# MOSFET_JUNCTION.net
KiCad netlist of a schematic drawn in Altium Designer
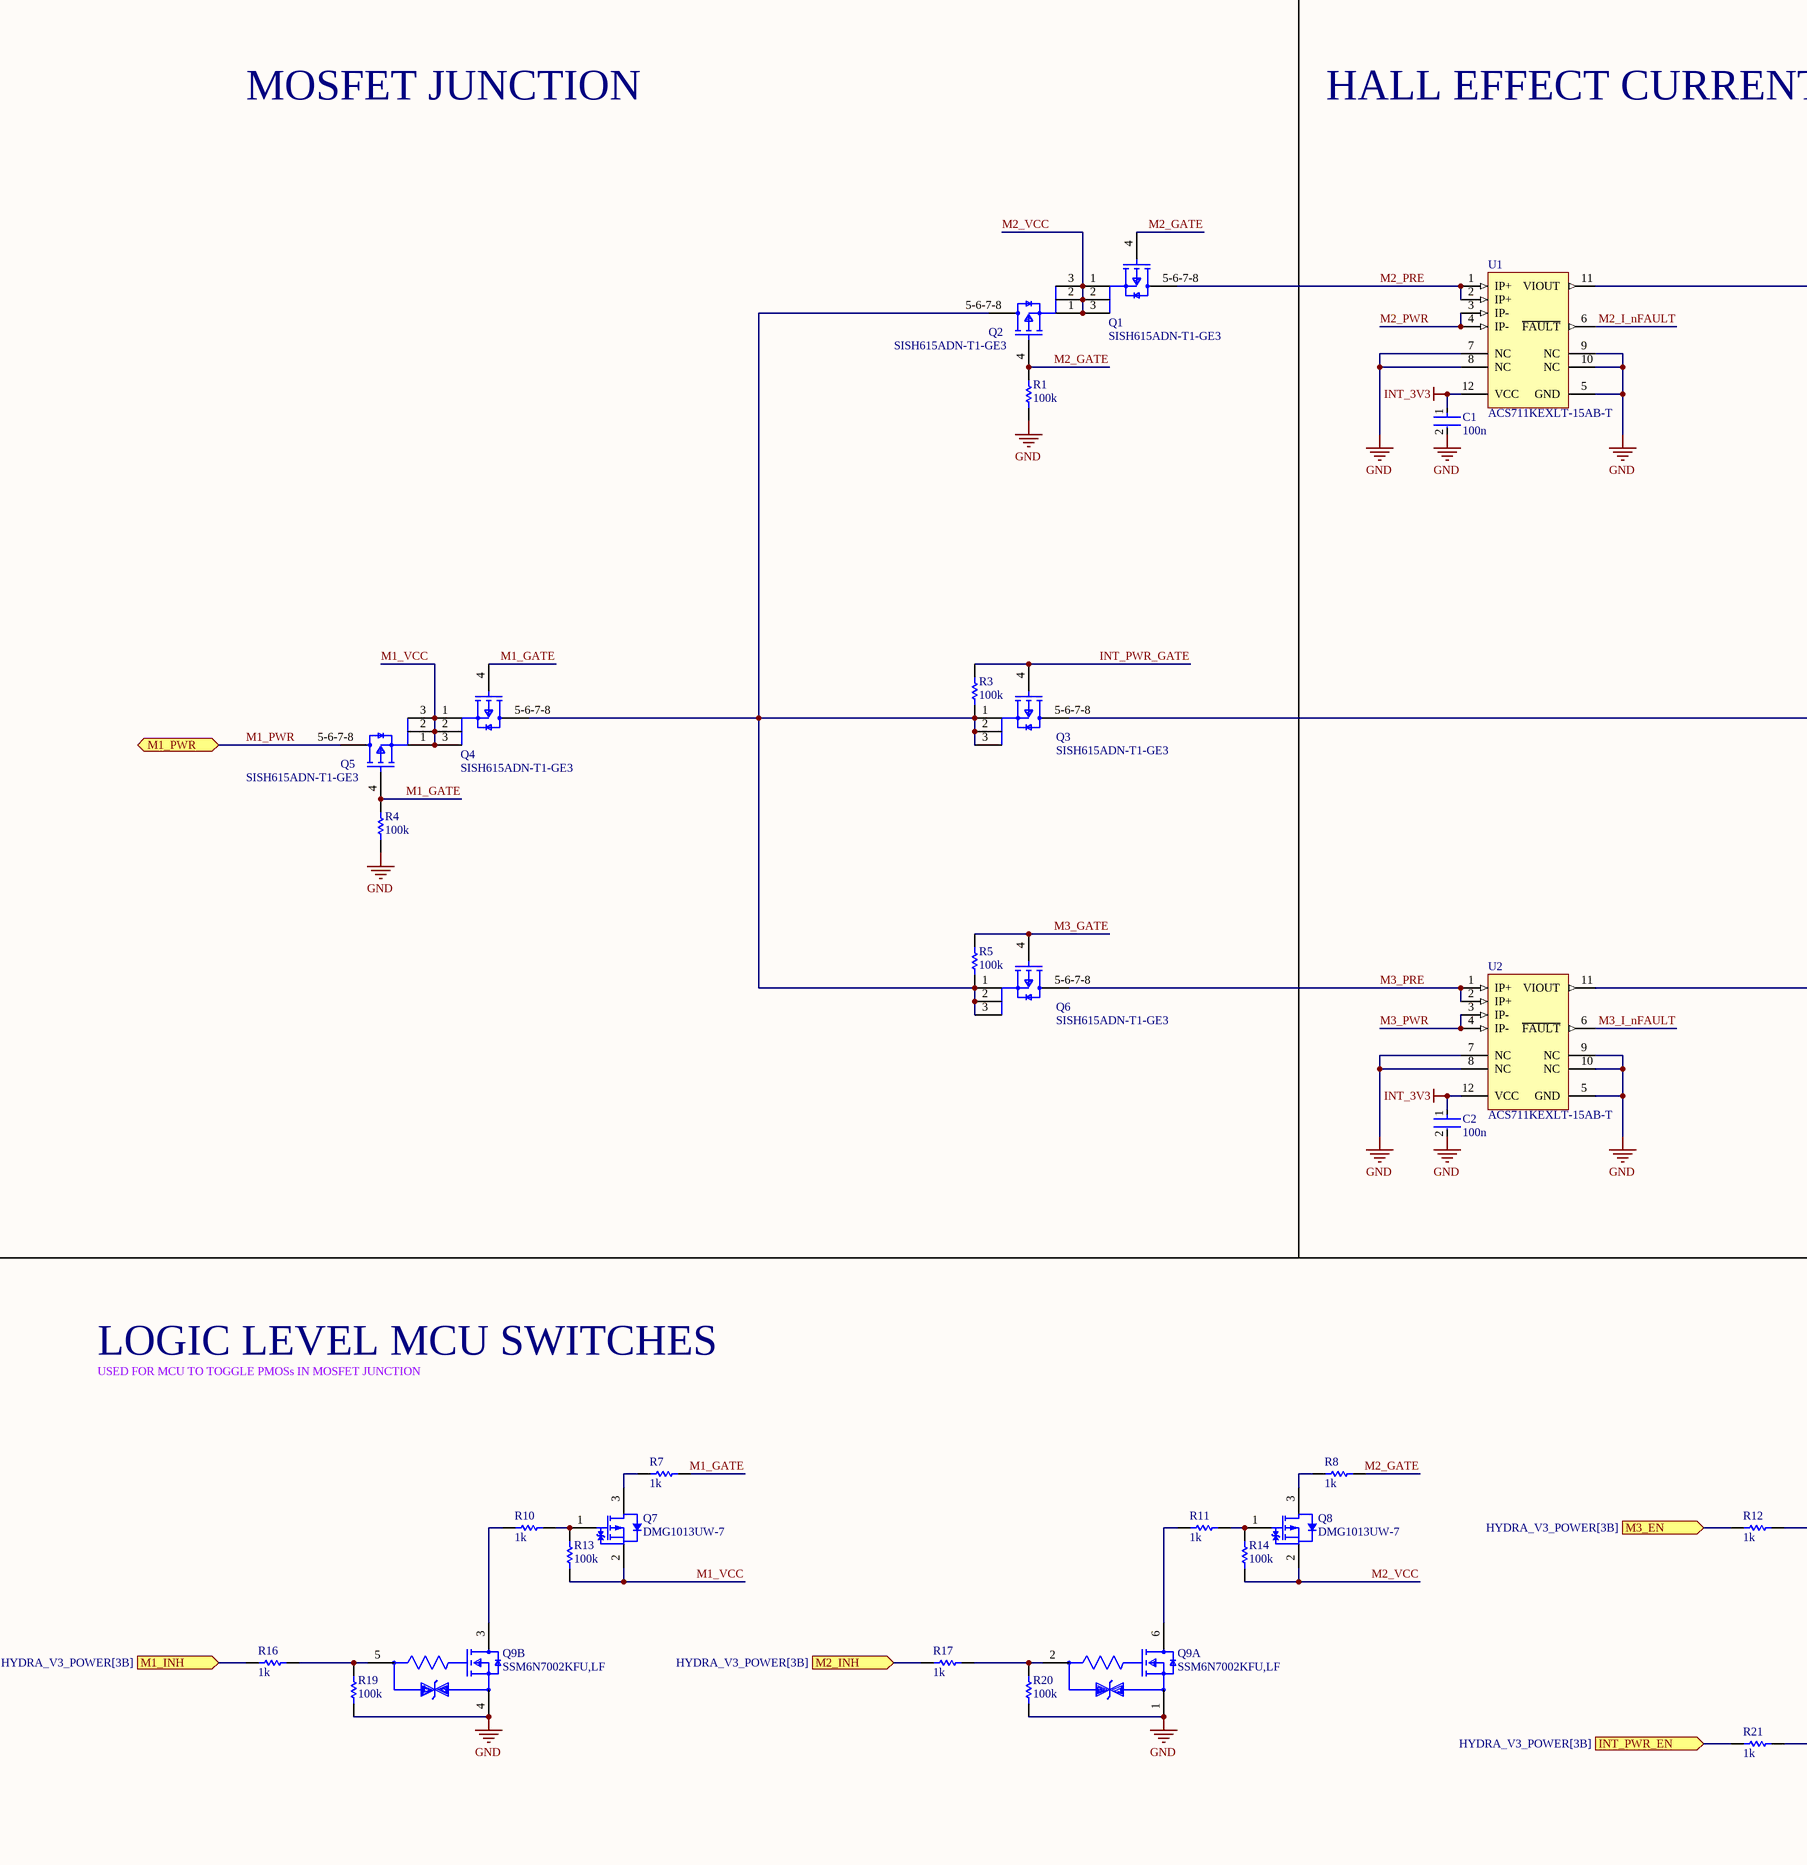
[diagram p0: MOSFET_JUNCTION.SchDoc, left]
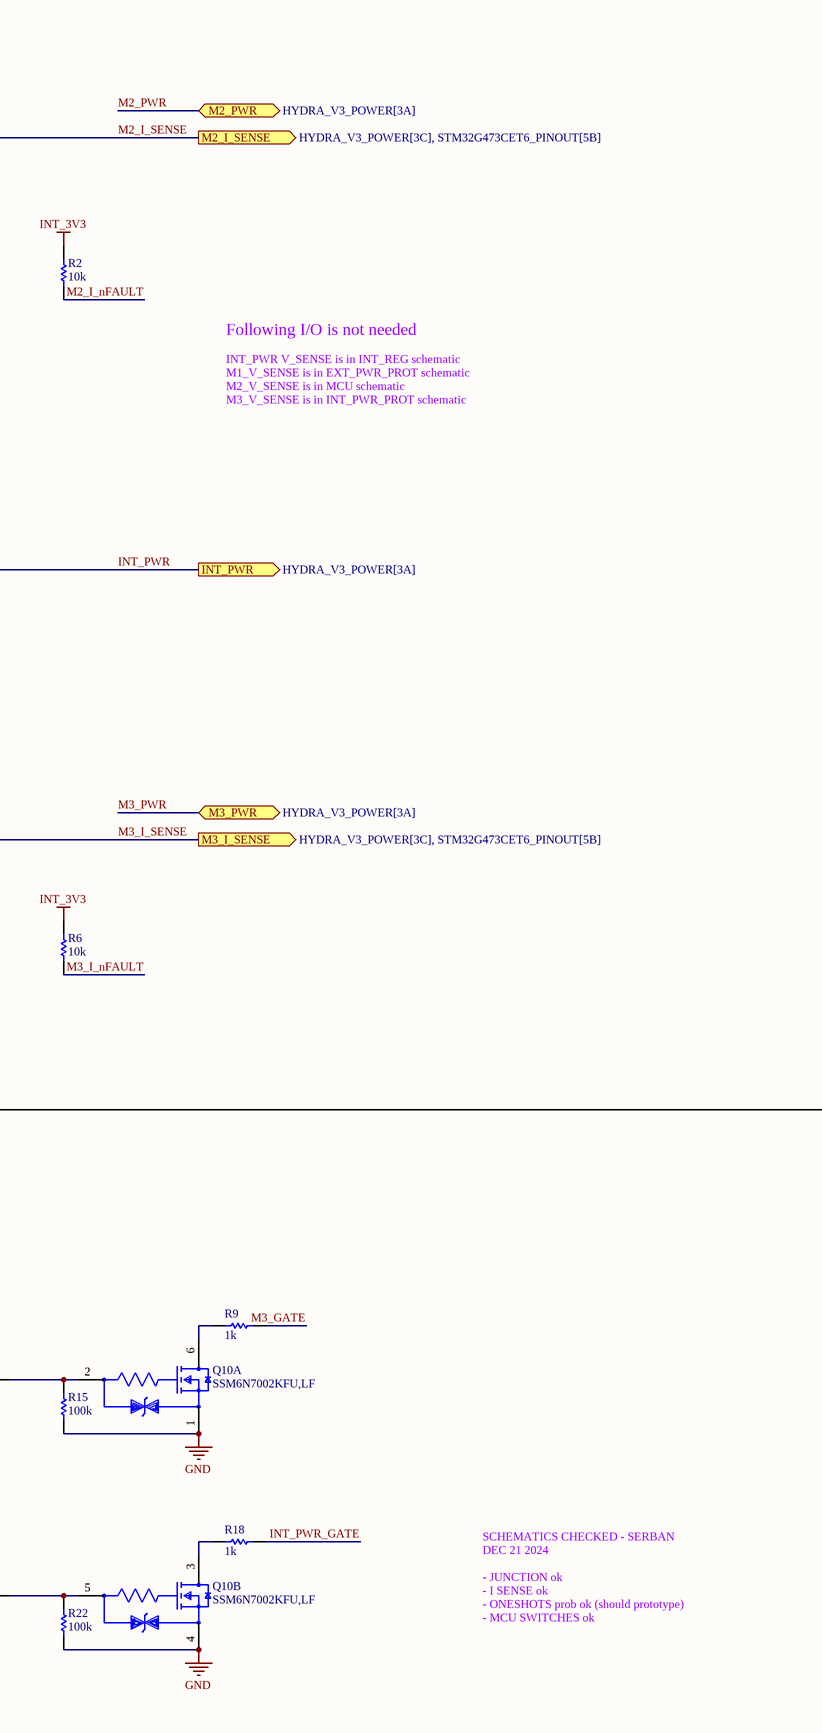
[diagram p1: MOSFET_JUNCTION.SchDoc, right]

(export (version "E")
  (design (tool "Eeschema 10.0.6"))
  (components
    (comp (ref "C1")
      (value "100n")
      (footprint "FP-0402-L_1_0_0_05-W_0_5-IPC_A")
      (description "LARGE PADS, 0402 CAP, CHANGE COMMENT TO MATCH REAL P/N")
      (libsource (lib "Space Concordia") (part "b4654b650e69147ec39a6b967a45e02"))
    )
    (comp (ref "C2")
      (value "100n")
      (footprint "FP-0402-L_1_0_0_05-W_0_5-IPC_A")
      (description "LARGE PADS, 0402 CAP, CHANGE COMMENT TO MATCH REAL P/N")
      (libsource (lib "Space Concordia") (part "b4654b650e69147ec39a6b967a45e02"))
    )
    (comp (ref "Q1")
      (value "SISH615ADN-T1-GE3")
      (footprint "SISH615ADN-T1-GE3-Footprint-1")
      (description "Trans MOSFET P-CH 20V 22.1A 8-Pin PowerPAK 1212 EP T/R")
      (libsource (lib "Space Concordia") (part "CMP-013-00036-4"))
    )
    (comp (ref "Q2")
      (value "SISH615ADN-T1-GE3")
      (footprint "SISH615ADN-T1-GE3-Footprint-1")
      (description "Trans MOSFET P-CH 20V 22.1A 8-Pin PowerPAK 1212 EP T/R")
      (libsource (lib "Space Concordia") (part "CMP-013-00036-4"))
    )
    (comp (ref "Q3")
      (value "SISH615ADN-T1-GE3")
      (footprint "SISH615ADN-T1-GE3-Footprint-1")
      (description "Trans MOSFET P-CH 20V 22.1A 8-Pin PowerPAK 1212 EP T/R")
      (libsource (lib "Space Concordia") (part "CMP-013-00036-4"))
    )
    (comp (ref "Q4")
      (value "SISH615ADN-T1-GE3")
      (footprint "SISH615ADN-T1-GE3-Footprint-1")
      (description "Trans MOSFET P-CH 20V 22.1A 8-Pin PowerPAK 1212 EP T/R")
      (libsource (lib "Space Concordia") (part "CMP-013-00036-4"))
    )
    (comp (ref "Q5")
      (value "SISH615ADN-T1-GE3")
      (footprint "SISH615ADN-T1-GE3-Footprint-1")
      (description "Trans MOSFET P-CH 20V 22.1A 8-Pin PowerPAK 1212 EP T/R")
      (libsource (lib "Space Concordia") (part "CMP-013-00036-4"))
    )
    (comp (ref "Q6")
      (value "SISH615ADN-T1-GE3")
      (footprint "SISH615ADN-T1-GE3-Footprint-1")
      (description "Trans MOSFET P-CH 20V 22.1A 8-Pin PowerPAK 1212 EP T/R")
      (libsource (lib "Space Concordia") (part "CMP-013-00036-4"))
    )
    (comp (ref "Q7")
      (value "DMG1013UW-7")
      (footprint "DIOD-SOT323-3_V")
      (fields (field (name "MANUFACTURER") "Diodes Inc"))
      (libsource (lib "Altium Content Vault") (part "PEMOS-GSD-3_C"))
    )
    (comp (ref "Q8")
      (value "DMG1013UW-7")
      (footprint "DIOD-SOT323-3_V")
      (fields (field (name "MANUFACTURER") "Diodes Inc"))
      (libsource (lib "Altium Content Vault") (part "PEMOS-GSD-3_C"))
    )
    (comp (ref "Q9")
      (value "SSM6N7002KFU,LF")
      (footprint "FP-SSOP6-P-0_65A-MFG")
      (description "MOSFET 2N-CH 60V 0.3A")
      (libsource (lib "Altium Content Vault") (part "088aa6ac103fdeebe0d1c52ece6b7b9"))
    )
    (comp (ref "Q10")
      (value "SSM6N7002KFU,LF")
      (footprint "FP-SSOP6-P-0_65A-MFG")
      (description "MOSFET 2N-CH 60V 0.3A")
      (libsource (lib "Altium Content Vault") (part "088aa6ac103fdeebe0d1c52ece6b7b9"))
    )
    (comp (ref "R1")
      (value "100k")
      (footprint "R0603B")
      (description "Resistor")
      (libsource (lib "Space Concordia") (part "Resistor"))
    )
    (comp (ref "R2")
      (value "10k")
      (footprint "R0603B")
      (description "Resistor")
      (libsource (lib "Space Concordia") (part "Resistor"))
    )
    (comp (ref "R3")
      (value "100k")
      (footprint "R0603B")
      (description "Resistor")
      (libsource (lib "Space Concordia") (part "Resistor"))
    )
    (comp (ref "R4")
      (value "100k")
      (footprint "R0603B")
      (description "Resistor")
      (libsource (lib "Space Concordia") (part "Resistor"))
    )
    (comp (ref "R5")
      (value "100k")
      (footprint "R0603B")
      (description "Resistor")
      (libsource (lib "Space Concordia") (part "Resistor"))
    )
    (comp (ref "R6")
      (value "10k")
      (footprint "R0603B")
      (description "Resistor")
      (libsource (lib "Space Concordia") (part "Resistor"))
    )
    (comp (ref "R7")
      (value "1k")
      (footprint "R0603B")
      (description "Resistor")
      (libsource (lib "Space Concordia") (part "Resistor"))
    )
    (comp (ref "R8")
      (value "1k")
      (footprint "R0603B")
      (description "Resistor")
      (libsource (lib "Space Concordia") (part "Resistor"))
    )
    (comp (ref "R9")
      (value "1k")
      (footprint "R0603B")
      (description "Resistor")
      (libsource (lib "Space Concordia") (part "Resistor"))
    )
    (comp (ref "R10")
      (value "1k")
      (footprint "R0603B")
      (description "Resistor")
      (libsource (lib "Space Concordia") (part "Resistor"))
    )
    (comp (ref "R11")
      (value "1k")
      (footprint "R0603B")
      (description "Resistor")
      (libsource (lib "Space Concordia") (part "Resistor"))
    )
    (comp (ref "R12")
      (value "1k")
      (footprint "R0603B")
      (description "Resistor")
      (libsource (lib "Space Concordia") (part "Resistor"))
    )
    (comp (ref "R13")
      (value "100k")
      (footprint "R0603B")
      (description "Resistor")
      (libsource (lib "Space Concordia") (part "Resistor"))
    )
    (comp (ref "R14")
      (value "100k")
      (footprint "R0603B")
      (description "Resistor")
      (libsource (lib "Space Concordia") (part "Resistor"))
    )
    (comp (ref "R15")
      (value "100k")
      (footprint "R0603B")
      (description "Resistor")
      (libsource (lib "Space Concordia") (part "Resistor"))
    )
    (comp (ref "R16")
      (value "1k")
      (footprint "R0603B")
      (description "Resistor")
      (libsource (lib "Space Concordia") (part "Resistor"))
    )
    (comp (ref "R17")
      (value "1k")
      (footprint "R0603B")
      (description "Resistor")
      (libsource (lib "Space Concordia") (part "Resistor"))
    )
    (comp (ref "R18")
      (value "1k")
      (footprint "R0603B")
      (description "Resistor")
      (libsource (lib "Space Concordia") (part "Resistor"))
    )
    (comp (ref "R19")
      (value "100k")
      (footprint "R0603B")
      (description "Resistor")
      (libsource (lib "Space Concordia") (part "Resistor"))
    )
    (comp (ref "R20")
      (value "100k")
      (footprint "R0603B")
      (description "Resistor")
      (libsource (lib "Space Concordia") (part "Resistor"))
    )
    (comp (ref "R21")
      (value "1k")
      (footprint "R0603B")
      (description "Resistor")
      (libsource (lib "Space Concordia") (part "Resistor"))
    )
    (comp (ref "R22")
      (value "100k")
      (footprint "R0603B")
      (description "Resistor")
      (libsource (lib "Space Concordia") (part "Resistor"))
    )
    (comp (ref "U1")
      (value "ACS711KEXLT-15AB-T")
      (footprint "ALEG-EX-12_V")
      (libsource (lib "Altium Content Vault") (part "ALEG-ACS711-QFN-12"))
    )
    (comp (ref "U2")
      (value "ACS711KEXLT-15AB-T")
      (footprint "ALEG-EX-12_V")
      (libsource (lib "Altium Content Vault") (part "ALEG-ACS711-QFN-12"))
    )
  )
  (nets
    (net (code "1") (name "/INT_PWR") (class "Default")
      (node (ref "Q3") (pin "5-6-7-8") (pinfunction "D_5-6-7-8") (pintype "passive"))
    )
    (net (code "2") (name "/INT_PWR_EN") (class "Default")
      (node (ref "R21") (pin "2") (pinfunction "2_2") (pintype "passive"))
    )
    (net (code "3") (name "/INT_PWR_GATE") (class "Default")
      (node (ref "Q3") (pin "4") (pinfunction "G_4") (pintype "passive"))
      (node (ref "R18") (pin "1") (pinfunction "1_1") (pintype "passive"))
      (node (ref "R3") (pin "2") (pinfunction "2_2") (pintype "passive"))
    )
    (net (code "4") (name "/M1_GATE") (class "Default")
      (node (ref "Q4") (pin "4") (pinfunction "G_4") (pintype "passive"))
      (node (ref "Q5") (pin "4") (pinfunction "G_4") (pintype "passive"))
      (node (ref "R4") (pin "2") (pinfunction "2_2") (pintype "passive"))
      (node (ref "R7") (pin "1") (pinfunction "1_1") (pintype "passive"))
    )
    (net (code "5") (name "/M1_INH") (class "Default")
      (node (ref "R16") (pin "2") (pinfunction "2_2") (pintype "passive"))
    )
    (net (code "6") (name "/M1_PWR") (class "Default")
      (node (ref "Q5") (pin "5-6-7-8") (pinfunction "D_5-6-7-8") (pintype "passive"))
    )
    (net (code "7") (name "/M1_VCC") (class "Default")
      (node (ref "Q4") (pin "1") (pinfunction "S_1") (pintype "passive"))
      (node (ref "Q4") (pin "2") (pinfunction "S_2") (pintype "passive"))
      (node (ref "Q4") (pin "3") (pinfunction "S_3") (pintype "passive"))
      (node (ref "Q5") (pin "1") (pinfunction "S_1") (pintype "passive"))
      (node (ref "Q5") (pin "2") (pinfunction "S_2") (pintype "passive"))
      (node (ref "Q5") (pin "3") (pinfunction "S_3") (pintype "passive"))
      (node (ref "Q7") (pin "2") (pinfunction "S_2") (pintype "passive"))
      (node (ref "R13") (pin "2") (pinfunction "2_2") (pintype "passive"))
    )
    (net (code "8") (name "/M2_GATE") (class "Default")
      (node (ref "Q1") (pin "4") (pinfunction "G_4") (pintype "passive"))
      (node (ref "Q2") (pin "4") (pinfunction "G_4") (pintype "passive"))
      (node (ref "R1") (pin "2") (pinfunction "2_2") (pintype "passive"))
      (node (ref "R8") (pin "1") (pinfunction "1_1") (pintype "passive"))
    )
    (net (code "9") (name "/M2_INH") (class "Default")
      (node (ref "R17") (pin "2") (pinfunction "2_2") (pintype "passive"))
    )
    (net (code "10") (name "/M2_I_SENSE") (class "Default")
      (node (ref "U1") (pin "11") (pinfunction "VIOUT_11") (pintype "output"))
    )
    (net (code "11") (name "/M2_I_nFAULT") (class "Default")
      (node (ref "R2") (pin "1") (pinfunction "1_1") (pintype "passive"))
      (node (ref "U1") (pin "6") (pinfunction "~{FAULT}_6") (pintype "output"))
    )
    (net (code "12") (name "/M2_PRE") (class "Default")
      (node (ref "Q1") (pin "5-6-7-8") (pinfunction "D_5-6-7-8") (pintype "passive"))
      (node (ref "U1") (pin "1") (pinfunction "IP+_1") (pintype "input"))
      (node (ref "U1") (pin "2") (pinfunction "IP+_2") (pintype "input"))
    )
    (net (code "13") (name "/M2_PWR") (class "Default")
      (node (ref "U1") (pin "3") (pinfunction "IP-_3") (pintype "input"))
      (node (ref "U1") (pin "4") (pinfunction "IP-_4") (pintype "input"))
    )
    (net (code "14") (name "/M2_VCC") (class "Default")
      (node (ref "Q1") (pin "1") (pinfunction "S_1") (pintype "passive"))
      (node (ref "Q1") (pin "2") (pinfunction "S_2") (pintype "passive"))
      (node (ref "Q1") (pin "3") (pinfunction "S_3") (pintype "passive"))
      (node (ref "Q2") (pin "1") (pinfunction "S_1") (pintype "passive"))
      (node (ref "Q2") (pin "2") (pinfunction "S_2") (pintype "passive"))
      (node (ref "Q2") (pin "3") (pinfunction "S_3") (pintype "passive"))
      (node (ref "Q8") (pin "2") (pinfunction "S_2") (pintype "passive"))
      (node (ref "R14") (pin "2") (pinfunction "2_2") (pintype "passive"))
    )
    (net (code "15") (name "/M3_EN") (class "Default")
      (node (ref "R12") (pin "2") (pinfunction "2_2") (pintype "passive"))
    )
    (net (code "16") (name "/M3_GATE") (class "Default")
      (node (ref "Q6") (pin "4") (pinfunction "G_4") (pintype "passive"))
      (node (ref "R5") (pin "2") (pinfunction "2_2") (pintype "passive"))
      (node (ref "R9") (pin "1") (pinfunction "1_1") (pintype "passive"))
    )
    (net (code "17") (name "/M3_I_SENSE") (class "Default")
      (node (ref "U2") (pin "11") (pinfunction "VIOUT_11") (pintype "output"))
    )
    (net (code "18") (name "/M3_I_nFAULT") (class "Default")
      (node (ref "R6") (pin "1") (pinfunction "1_1") (pintype "passive"))
      (node (ref "U2") (pin "6") (pinfunction "~{FAULT}_6") (pintype "output"))
    )
    (net (code "19") (name "/M3_PRE") (class "Default")
      (node (ref "Q6") (pin "5-6-7-8") (pinfunction "D_5-6-7-8") (pintype "passive"))
      (node (ref "U2") (pin "1") (pinfunction "IP+_1") (pintype "input"))
      (node (ref "U2") (pin "2") (pinfunction "IP+_2") (pintype "input"))
    )
    (net (code "20") (name "/M3_PWR") (class "Default")
      (node (ref "U2") (pin "3") (pinfunction "IP-_3") (pintype "input"))
      (node (ref "U2") (pin "4") (pinfunction "IP-_4") (pintype "input"))
    )
    (net (code "21") (name "GND") (class "Default")
      (node (ref "C1") (pin "2") (pinfunction "2_2") (pintype "passive"))
      (node (ref "C2") (pin "2") (pinfunction "2_2") (pintype "passive"))
      (node (ref "Q10") (pin "1") (pinfunction "Source1_1") (pintype "passive"))
      (node (ref "Q10") (pin "4") (pinfunction "Source2_4") (pintype "passive"))
      (node (ref "Q9") (pin "1") (pinfunction "Source1_1") (pintype "passive"))
      (node (ref "Q9") (pin "4") (pinfunction "Source2_4") (pintype "passive"))
      (node (ref "R1") (pin "1") (pinfunction "1_1") (pintype "passive"))
      (node (ref "R15") (pin "1") (pinfunction "1_1") (pintype "passive"))
      (node (ref "R19") (pin "1") (pinfunction "1_1") (pintype "passive"))
      (node (ref "R20") (pin "1") (pinfunction "1_1") (pintype "passive"))
      (node (ref "R22") (pin "1") (pinfunction "1_1") (pintype "passive"))
      (node (ref "R4") (pin "1") (pinfunction "1_1") (pintype "passive"))
      (node (ref "U1") (pin "10") (pinfunction "NC_10") (pintype "passive"))
      (node (ref "U1") (pin "5") (pinfunction "GND_5") (pintype "power_in"))
      (node (ref "U1") (pin "7") (pinfunction "NC_7") (pintype "passive"))
      (node (ref "U1") (pin "8") (pinfunction "NC_8") (pintype "passive"))
      (node (ref "U1") (pin "9") (pinfunction "NC_9") (pintype "passive"))
      (node (ref "U2") (pin "10") (pinfunction "NC_10") (pintype "passive"))
      (node (ref "U2") (pin "5") (pinfunction "GND_5") (pintype "power_in"))
      (node (ref "U2") (pin "7") (pinfunction "NC_7") (pintype "passive"))
      (node (ref "U2") (pin "8") (pinfunction "NC_8") (pintype "passive"))
      (node (ref "U2") (pin "9") (pinfunction "NC_9") (pintype "passive"))
    )
    (net (code "22") (name "INT_3V3") (class "Default")
      (node (ref "C1") (pin "1") (pinfunction "1_1") (pintype "passive"))
      (node (ref "C2") (pin "1") (pinfunction "1_1") (pintype "passive"))
      (node (ref "R2") (pin "2") (pinfunction "2_2") (pintype "passive"))
      (node (ref "R6") (pin "2") (pinfunction "2_2") (pintype "passive"))
      (node (ref "U1") (pin "12") (pinfunction "VCC_12") (pintype "power_in"))
      (node (ref "U2") (pin "12") (pinfunction "VCC_12") (pintype "power_in"))
    )
    (net (code "23") (name "Net-(Q2-D)") (class "Default")
      (node (ref "Q2") (pin "5-6-7-8") (pinfunction "D_5-6-7-8") (pintype "passive"))
      (node (ref "Q3") (pin "1") (pinfunction "S_1") (pintype "passive"))
      (node (ref "Q3") (pin "2") (pinfunction "S_2") (pintype "passive"))
      (node (ref "Q3") (pin "3") (pinfunction "S_3") (pintype "passive"))
      (node (ref "Q4") (pin "5-6-7-8") (pinfunction "D_5-6-7-8") (pintype "passive"))
      (node (ref "Q6") (pin "1") (pinfunction "S_1") (pintype "passive"))
      (node (ref "Q6") (pin "2") (pinfunction "S_2") (pintype "passive"))
      (node (ref "Q6") (pin "3") (pinfunction "S_3") (pintype "passive"))
      (node (ref "R3") (pin "1") (pinfunction "1_1") (pintype "passive"))
      (node (ref "R5") (pin "1") (pinfunction "1_1") (pintype "passive"))
    )
    (net (code "24") (name "Net-(Q7-D)") (class "Default")
      (node (ref "Q7") (pin "3") (pinfunction "D_3") (pintype "passive"))
      (node (ref "R7") (pin "2") (pinfunction "2_2") (pintype "passive"))
    )
    (net (code "25") (name "Net-(Q7-G)") (class "Default")
      (node (ref "Q7") (pin "1") (pinfunction "G_1") (pintype "passive"))
      (node (ref "R10") (pin "1") (pinfunction "1_1") (pintype "passive"))
      (node (ref "R13") (pin "1") (pinfunction "1_1") (pintype "passive"))
    )
    (net (code "26") (name "Net-(Q8-D)") (class "Default")
      (node (ref "Q8") (pin "3") (pinfunction "D_3") (pintype "passive"))
      (node (ref "R8") (pin "2") (pinfunction "2_2") (pintype "passive"))
    )
    (net (code "27") (name "Net-(Q8-G)") (class "Default")
      (node (ref "Q8") (pin "1") (pinfunction "G_1") (pintype "passive"))
      (node (ref "R11") (pin "1") (pinfunction "1_1") (pintype "passive"))
      (node (ref "R14") (pin "1") (pinfunction "1_1") (pintype "passive"))
    )
    (net (code "28") (name "Net-(Q9A-Drain1)") (class "Default")
      (node (ref "Q9") (pin "6") (pinfunction "Drain1_6") (pintype "passive"))
      (node (ref "R11") (pin "2") (pinfunction "2_2") (pintype "passive"))
    )
    (net (code "29") (name "Net-(Q9A-Gate1)") (class "Default")
      (node (ref "Q9") (pin "2") (pinfunction "Gate1_2") (pintype "passive"))
      (node (ref "R17") (pin "1") (pinfunction "1_1") (pintype "passive"))
      (node (ref "R20") (pin "2") (pinfunction "2_2") (pintype "passive"))
    )
    (net (code "30") (name "Net-(Q9B-Drain2)") (class "Default")
      (node (ref "Q9") (pin "3") (pinfunction "Drain2_3") (pintype "passive"))
      (node (ref "R10") (pin "2") (pinfunction "2_2") (pintype "passive"))
    )
    (net (code "31") (name "Net-(Q9B-Gate2)") (class "Default")
      (node (ref "Q9") (pin "5") (pinfunction "Gate2_5") (pintype "passive"))
      (node (ref "R16") (pin "1") (pinfunction "1_1") (pintype "passive"))
      (node (ref "R19") (pin "2") (pinfunction "2_2") (pintype "passive"))
    )
    (net (code "32") (name "Net-(Q10A-Drain1)") (class "Default")
      (node (ref "Q10") (pin "6") (pinfunction "Drain1_6") (pintype "passive"))
      (node (ref "R9") (pin "2") (pinfunction "2_2") (pintype "passive"))
    )
    (net (code "33") (name "Net-(Q10A-Gate1)") (class "Default")
      (node (ref "Q10") (pin "2") (pinfunction "Gate1_2") (pintype "passive"))
      (node (ref "R12") (pin "1") (pinfunction "1_1") (pintype "passive"))
      (node (ref "R15") (pin "2") (pinfunction "2_2") (pintype "passive"))
    )
    (net (code "34") (name "Net-(Q10B-Drain2)") (class "Default")
      (node (ref "Q10") (pin "3") (pinfunction "Drain2_3") (pintype "passive"))
      (node (ref "R18") (pin "2") (pinfunction "2_2") (pintype "passive"))
    )
    (net (code "35") (name "Net-(Q10B-Gate2)") (class "Default")
      (node (ref "Q10") (pin "5") (pinfunction "Gate2_5") (pintype "passive"))
      (node (ref "R21") (pin "1") (pinfunction "1_1") (pintype "passive"))
      (node (ref "R22") (pin "2") (pinfunction "2_2") (pintype "passive"))
    )
  )
)
